# mapleSDuino-V0_1_013-eagle7.net
KiCad netlist of a schematic drawn in EAGLE
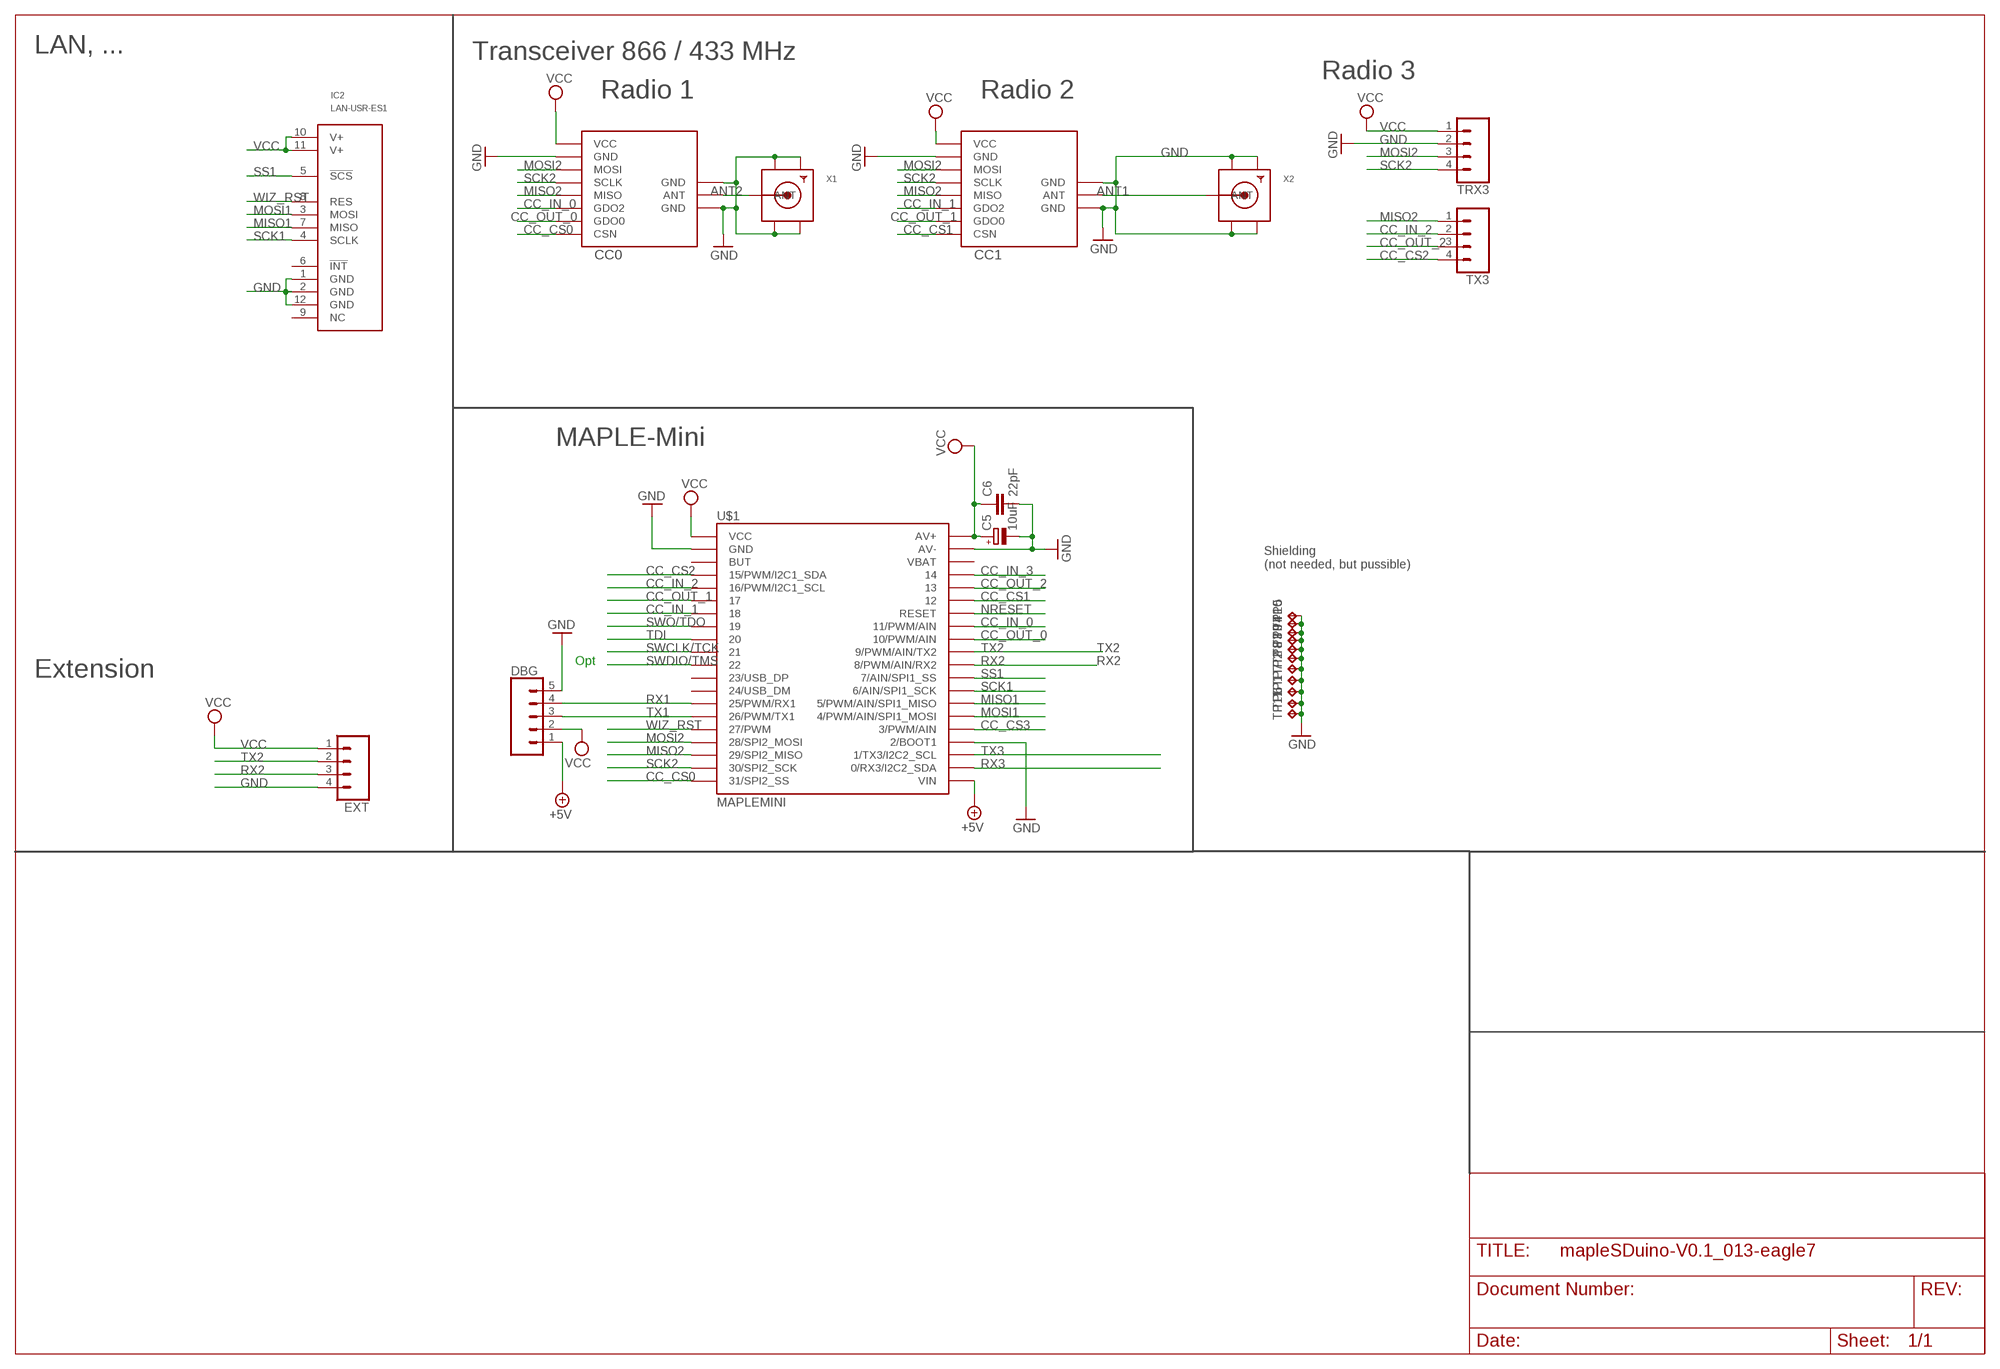
[diagram p0: schematic, sheet 1]

(export (version "E")
  (design (tool "Eeschema 10.0.6"))
  (components
    (comp (ref "C5")
      (value "10uF")
      (footprint "eagle-import:R_2012-12W")
      (libsource (lib "eagle-import") (part "CPOL-EUR/2012-12W"))
    )
    (comp (ref "C6")
      (value "22pF")
      (footprint "eagle-import:C0805")
      (libsource (lib "eagle-import") (part "C-EUC0805"))
    )
    (comp (ref "CC0")
      (value "CC1101")
      (footprint "eagle-import:CC1101_MODULE1_SMD")
      (libsource (lib "eagle-import") (part "CC1101_MODULE1SMD"))
    )
    (comp (ref "CC1")
      (value "CC1101_MODULE1SMD")
      (footprint "eagle-import:CC1101_MODULE1_SMD")
      (libsource (lib "eagle-import") (part "CC1101_MODULE1SMD"))
    )
    (comp (ref "DBG")
      (value "CONN_05LOCK")
      (footprint "eagle-import:1X05_LOCK")
      (libsource (lib "eagle-import") (part "CONN_05LOCK"))
    )
    (comp (ref "EXT")
      (value "CONN_04PTH")
      (footprint "eagle-import:1X04")
      (libsource (lib "eagle-import") (part "CONN_04PTH"))
    )
    (comp (ref "IC2")
      (value "LAN-USR-ES1")
      (footprint "eagle-import:USR-ES1")
      (libsource (lib "eagle-import") (part "LAN-USR-ES1"))
    )
    (comp (ref "TP1")
      (value "TPTP06SQ")
      (footprint "eagle-import:TP06SQ")
      (libsource (lib "eagle-import") (part "TPTP06SQ"))
    )
    (comp (ref "TP2")
      (value "TPTP06SQ")
      (footprint "eagle-import:TP06SQ")
      (libsource (lib "eagle-import") (part "TPTP06SQ"))
    )
    (comp (ref "TP3")
      (value "TPTP06SQ")
      (footprint "eagle-import:TP06SQ")
      (libsource (lib "eagle-import") (part "TPTP06SQ"))
    )
    (comp (ref "TP4")
      (value "TPTP06SQ")
      (footprint "eagle-import:TP06SQ")
      (libsource (lib "eagle-import") (part "TPTP06SQ"))
    )
    (comp (ref "TP5")
      (value "TPTP06SQ")
      (footprint "eagle-import:TP06SQ")
      (libsource (lib "eagle-import") (part "TPTP06SQ"))
    )
    (comp (ref "TP6")
      (value "TPTP06SQ")
      (footprint "eagle-import:TP06SQ")
      (libsource (lib "eagle-import") (part "TPTP06SQ"))
    )
    (comp (ref "TP7")
      (value "TPTP06SQ")
      (footprint "eagle-import:TP06SQ")
      (libsource (lib "eagle-import") (part "TPTP06SQ"))
    )
    (comp (ref "TP8")
      (value "TPTP06SQ")
      (footprint "eagle-import:TP06SQ")
      (libsource (lib "eagle-import") (part "TPTP06SQ"))
    )
    (comp (ref "TP9")
      (value "TPTP06SQ")
      (footprint "eagle-import:TP06SQ")
      (libsource (lib "eagle-import") (part "TPTP06SQ"))
    )
    (comp (ref "TP10")
      (value "TPTP06SQ")
      (footprint "eagle-import:TP06SQ")
      (libsource (lib "eagle-import") (part "TPTP06SQ"))
    )
    (comp (ref "TP11")
      (value "TPTP06SQ")
      (footprint "eagle-import:TP06SQ")
      (libsource (lib "eagle-import") (part "TPTP06SQ"))
    )
    (comp (ref "TRX3")
      (value "CONN_04PTH")
      (footprint "eagle-import:1X04")
      (libsource (lib "eagle-import") (part "CONN_04PTH"))
    )
    (comp (ref "TX3")
      (value "CONN_04PTH")
      (footprint "eagle-import:1X04")
      (libsource (lib "eagle-import") (part "CONN_04PTH"))
    )
    (comp (ref "U$1")
      (value "MAPLEMINI")
      (footprint "eagle-import:20-DIP")
      (libsource (lib "eagle-import") (part "MAPLEMINI"))
    )
    (comp (ref "X1")
      (value "SMACONNECTOR_EDGE")
      (footprint "eagle-import:SMA_EDGELAUNCH")
      (libsource (lib "eagle-import") (part "SMACONNECTOR_EDGE"))
    )
    (comp (ref "X2")
      (value "SMACONNECTOR_EDGE")
      (footprint "eagle-import:SMA_EDGELAUNCH")
      (libsource (lib "eagle-import") (part "SMACONNECTOR_EDGE"))
    )
  )
  (nets
    (net (code "1") (name "+5V") (class "Default")
      (node (ref "DBG") (pin "1") (pinfunction "1_1") (pintype "passive"))
      (node (ref "U$1") (pin "21") (pinfunction "VIN_21") (pintype "bidirectional"))
    )
    (net (code "2") (name "/ANT1") (class "Default")
      (node (ref "CC1") (pin "ANT") (pinfunction "ANT_ANT") (pintype "output"))
      (node (ref "X2") (pin "P") (pinfunction "ANT_P") (pintype "bidirectional"))
    )
    (net (code "3") (name "/ANT2") (class "Default")
      (node (ref "CC0") (pin "ANT") (pinfunction "ANT_ANT") (pintype "output"))
      (node (ref "X1") (pin "P") (pinfunction "ANT_P") (pintype "bidirectional"))
    )
    (net (code "4") (name "/CC_CS0") (class "Default")
      (node (ref "CC0") (pin "CSN") (pinfunction "CSN_CSN") (pintype "bidirectional"))
      (node (ref "U$1") (pin "20") (pinfunction "31/SPI2_SS_20") (pintype "bidirectional"))
    )
    (net (code "5") (name "/CC_CS1") (class "Default")
      (node (ref "CC1") (pin "CSN") (pinfunction "CSN_CSN") (pintype "bidirectional"))
      (node (ref "U$1") (pin "35") (pinfunction "12_35") (pintype "bidirectional"))
    )
    (net (code "6") (name "/CC_CS2") (class "Default")
      (node (ref "TX3") (pin "4") (pinfunction "4_4") (pintype "passive"))
      (node (ref "U$1") (pin "4") (pinfunction "15/PWM/I2C1_SDA_4") (pintype "bidirectional"))
    )
    (net (code "7") (name "/CC_CS3") (class "Default")
      (node (ref "U$1") (pin "25") (pinfunction "3/PWM/AIN_25") (pintype "bidirectional"))
    )
    (net (code "8") (name "/CC_IN_0") (class "Default")
      (node (ref "CC0") (pin "GDO2") (pinfunction "GDO2_GDO2") (pintype "bidirectional"))
      (node (ref "U$1") (pin "33") (pinfunction "11/PWM/AIN_33") (pintype "bidirectional"))
    )
    (net (code "9") (name "/CC_IN_1") (class "Default")
      (node (ref "CC1") (pin "GDO2") (pinfunction "GDO2_GDO2") (pintype "bidirectional"))
      (node (ref "U$1") (pin "7") (pinfunction "18_7") (pintype "bidirectional"))
    )
    (net (code "10") (name "/CC_IN_2") (class "Default")
      (node (ref "TX3") (pin "2") (pinfunction "2_2") (pintype "passive"))
      (node (ref "U$1") (pin "5") (pinfunction "16/PWM/I2C1_SCL_5") (pintype "bidirectional"))
    )
    (net (code "11") (name "/CC_IN_3") (class "Default")
      (node (ref "U$1") (pin "37") (pinfunction "14_37") (pintype "bidirectional"))
    )
    (net (code "12") (name "/CC_OUT_0") (class "Default")
      (node (ref "CC0") (pin "GDO0") (pinfunction "GDO0_GDO0") (pintype "bidirectional"))
      (node (ref "U$1") (pin "32") (pinfunction "10/PWM/AIN_32") (pintype "bidirectional"))
    )
    (net (code "13") (name "/CC_OUT_1") (class "Default")
      (node (ref "CC1") (pin "GDO0") (pinfunction "GDO0_GDO0") (pintype "bidirectional"))
      (node (ref "U$1") (pin "6") (pinfunction "17_6") (pintype "bidirectional"))
    )
    (net (code "14") (name "/CC_OUT_2") (class "Default")
      (node (ref "TX3") (pin "3") (pinfunction "3_3") (pintype "passive"))
      (node (ref "U$1") (pin "36") (pinfunction "13_36") (pintype "bidirectional"))
    )
    (net (code "15") (name "/MISO1") (class "Default")
      (node (ref "IC2") (pin "7") (pinfunction "MISO_7") (pintype "bidirectional"))
      (node (ref "U$1") (pin "27") (pinfunction "5/PWM/AIN/SPI1_MISO_27") (pintype "bidirectional"))
    )
    (net (code "16") (name "/MISO2") (class "Default")
      (node (ref "CC0") (pin "MISO") (pinfunction "MISO_MISO") (pintype "bidirectional"))
      (node (ref "CC1") (pin "MISO") (pinfunction "MISO_MISO") (pintype "bidirectional"))
      (node (ref "TX3") (pin "1") (pinfunction "1_1") (pintype "passive"))
      (node (ref "U$1") (pin "18") (pinfunction "29/SPI2_MISO_18") (pintype "bidirectional"))
    )
    (net (code "17") (name "/MOSI1") (class "Default")
      (node (ref "IC2") (pin "3") (pinfunction "MOSI_3") (pintype "bidirectional"))
      (node (ref "U$1") (pin "26") (pinfunction "4/PWM/AIN/SPI1_MOSI_26") (pintype "bidirectional"))
    )
    (net (code "18") (name "/MOSI2") (class "Default")
      (node (ref "CC0") (pin "MOSI") (pinfunction "MOSI_MOSI") (pintype "bidirectional"))
      (node (ref "CC1") (pin "MOSI") (pinfunction "MOSI_MOSI") (pintype "bidirectional"))
      (node (ref "TRX3") (pin "3") (pinfunction "3_3") (pintype "passive"))
      (node (ref "U$1") (pin "17") (pinfunction "28/SPI2_MOSI_17") (pintype "bidirectional"))
    )
    (net (code "19") (name "/NRESET") (class "Default")
      (node (ref "U$1") (pin "34") (pinfunction "RESET_34") (pintype "bidirectional"))
    )
    (net (code "20") (name "/RX1") (class "Default")
      (node (ref "DBG") (pin "4") (pinfunction "4_4") (pintype "passive"))
      (node (ref "U$1") (pin "14") (pinfunction "25/PWM/RX1_14") (pintype "bidirectional"))
    )
    (net (code "21") (name "/RX2") (class "Default")
      (node (ref "EXT") (pin "3") (pinfunction "3_3") (pintype "passive"))
      (node (ref "U$1") (pin "30") (pinfunction "8/PWM/AIN/RX2_30") (pintype "bidirectional"))
    )
    (net (code "22") (name "/RX3") (class "Default")
      (node (ref "U$1") (pin "22") (pinfunction "0/RX3/I2C2_SDA_22") (pintype "bidirectional"))
    )
    (net (code "23") (name "/SCK1") (class "Default")
      (node (ref "IC2") (pin "4") (pinfunction "SCLK_4") (pintype "input"))
      (node (ref "U$1") (pin "28") (pinfunction "6/AIN/SPI1_SCK_28") (pintype "bidirectional"))
    )
    (net (code "24") (name "/SCK2") (class "Default")
      (node (ref "CC0") (pin "SCLK") (pinfunction "SCLK_SCLK") (pintype "bidirectional"))
      (node (ref "CC1") (pin "SCLK") (pinfunction "SCLK_SCLK") (pintype "bidirectional"))
      (node (ref "TRX3") (pin "4") (pinfunction "4_4") (pintype "passive"))
      (node (ref "U$1") (pin "19") (pinfunction "30/SPI2_SCK_19") (pintype "bidirectional"))
    )
    (net (code "25") (name "/SS1") (class "Default")
      (node (ref "IC2") (pin "5") (pinfunction "~{SCS}_5") (pintype "input"))
      (node (ref "U$1") (pin "29") (pinfunction "7/AIN/SPI1_SS_29") (pintype "bidirectional"))
    )
    (net (code "26") (name "/SWCLK{slash}TCK") (class "Default")
      (node (ref "U$1") (pin "10") (pinfunction "21_10") (pintype "bidirectional"))
    )
    (net (code "27") (name "/SWDIO{slash}TMS") (class "Default")
      (node (ref "U$1") (pin "11") (pinfunction "22_11") (pintype "bidirectional"))
    )
    (net (code "28") (name "/SWO{slash}TDO") (class "Default")
      (node (ref "U$1") (pin "8") (pinfunction "19_8") (pintype "bidirectional"))
    )
    (net (code "29") (name "/TDI") (class "Default")
      (node (ref "U$1") (pin "9") (pinfunction "20_9") (pintype "bidirectional"))
    )
    (net (code "30") (name "/TX1") (class "Default")
      (node (ref "DBG") (pin "3") (pinfunction "3_3") (pintype "passive"))
      (node (ref "U$1") (pin "15") (pinfunction "26/PWM/TX1_15") (pintype "bidirectional"))
    )
    (net (code "31") (name "/TX2") (class "Default")
      (node (ref "EXT") (pin "2") (pinfunction "2_2") (pintype "passive"))
      (node (ref "U$1") (pin "31") (pinfunction "9/PWM/AIN/TX2_31") (pintype "bidirectional"))
    )
    (net (code "32") (name "/TX3") (class "Default")
      (node (ref "U$1") (pin "23") (pinfunction "1/TX3/I2C2_SCL_23") (pintype "bidirectional"))
    )
    (net (code "33") (name "/WIZ_RST") (class "Default")
      (node (ref "IC2") (pin "8") (pinfunction "RES_8") (pintype "input"))
      (node (ref "U$1") (pin "16") (pinfunction "27/PWM_16") (pintype "bidirectional"))
    )
    (net (code "34") (name "GND") (class "Default")
      (node (ref "C5") (pin "-") (pinfunction "-_-") (pintype "passive"))
      (node (ref "C6") (pin "2") (pinfunction "2_2") (pintype "passive"))
      (node (ref "CC0") (pin "GND@0") (pinfunction "GND_GND@0") (pintype "power_in"))
      (node (ref "CC0") (pin "GND@1") (pinfunction "GND_GND@1") (pintype "power_in"))
      (node (ref "CC0") (pin "GND@2") (pinfunction "GND_GND@2") (pintype "power_in"))
      (node (ref "CC1") (pin "GND@0") (pinfunction "GND_GND@0") (pintype "power_in"))
      (node (ref "CC1") (pin "GND@1") (pinfunction "GND_GND@1") (pintype "power_in"))
      (node (ref "CC1") (pin "GND@2") (pinfunction "GND_GND@2") (pintype "power_in"))
      (node (ref "DBG") (pin "5") (pinfunction "5_5") (pintype "passive"))
      (node (ref "EXT") (pin "4") (pinfunction "4_4") (pintype "passive"))
      (node (ref "IC2") (pin "1") (pinfunction "GND_1") (pintype "power_in"))
      (node (ref "IC2") (pin "12") (pinfunction "GND_12") (pintype "power_in"))
      (node (ref "IC2") (pin "2") (pinfunction "GND_2") (pintype "power_in"))
      (node (ref "TP1") (pin "TP") (pinfunction "TP_TP") (pintype "input"))
      (node (ref "TP10") (pin "TP") (pinfunction "TP_TP") (pintype "input"))
      (node (ref "TP11") (pin "TP") (pinfunction "TP_TP") (pintype "input"))
      (node (ref "TP2") (pin "TP") (pinfunction "TP_TP") (pintype "input"))
      (node (ref "TP3") (pin "TP") (pinfunction "TP_TP") (pintype "input"))
      (node (ref "TP4") (pin "TP") (pinfunction "TP_TP") (pintype "input"))
      (node (ref "TP5") (pin "TP") (pinfunction "TP_TP") (pintype "input"))
      (node (ref "TP6") (pin "TP") (pinfunction "TP_TP") (pintype "input"))
      (node (ref "TP7") (pin "TP") (pinfunction "TP_TP") (pintype "input"))
      (node (ref "TP8") (pin "TP") (pinfunction "TP_TP") (pintype "input"))
      (node (ref "TP9") (pin "TP") (pinfunction "TP_TP") (pintype "input"))
      (node (ref "TRX3") (pin "2") (pinfunction "2_2") (pintype "passive"))
      (node (ref "U$1") (pin "2") (pinfunction "GND_2") (pintype "bidirectional"))
      (node (ref "U$1") (pin "24") (pinfunction "2/BOOT1_24") (pintype "bidirectional"))
      (node (ref "U$1") (pin "39") (pinfunction "AV-_39") (pintype "bidirectional"))
      (node (ref "X1") (pin "GND@1") (pinfunction "GND4_GND@1") (pintype "power_in"))
      (node (ref "X1") (pin "GND@2") (pinfunction "GND3_GND@2") (pintype "power_in"))
      (node (ref "X1") (pin "GND@3") (pinfunction "GND2_GND@3") (pintype "power_in"))
      (node (ref "X1") (pin "GND@4") (pinfunction "GND1_GND@4") (pintype "power_in"))
      (node (ref "X2") (pin "GND@1") (pinfunction "GND4_GND@1") (pintype "power_in"))
      (node (ref "X2") (pin "GND@2") (pinfunction "GND3_GND@2") (pintype "power_in"))
      (node (ref "X2") (pin "GND@3") (pinfunction "GND2_GND@3") (pintype "power_in"))
      (node (ref "X2") (pin "GND@4") (pinfunction "GND1_GND@4") (pintype "power_in"))
    )
    (net (code "35") (name "VCC") (class "Default")
      (node (ref "C5") (pin "+") (pinfunction "+_+") (pintype "passive"))
      (node (ref "C6") (pin "1") (pinfunction "1_1") (pintype "passive"))
      (node (ref "CC0") (pin "VCC") (pinfunction "VCC_VCC") (pintype "power_in"))
      (node (ref "CC1") (pin "VCC") (pinfunction "VCC_VCC") (pintype "power_in"))
      (node (ref "DBG") (pin "2") (pinfunction "2_2") (pintype "passive"))
      (node (ref "EXT") (pin "1") (pinfunction "1_1") (pintype "passive"))
      (node (ref "IC2") (pin "10") (pinfunction "V+_10") (pintype "power_in"))
      (node (ref "IC2") (pin "11") (pinfunction "V+_11") (pintype "power_in"))
      (node (ref "TRX3") (pin "1") (pinfunction "1_1") (pintype "passive"))
      (node (ref "U$1") (pin "1") (pinfunction "VCC_1") (pintype "bidirectional"))
      (node (ref "U$1") (pin "40") (pinfunction "AV+_40") (pintype "bidirectional"))
    )
    (net (code "36") (name "unconnected-(IC2-NC-Pad9)") (class "Default")
      (node (ref "IC2") (pin "9") (pinfunction "NC_9") (pintype "no_connect"))
    )
    (net (code "37") (name "unconnected-(IC2-~{INT}-Pad6)") (class "Default")
      (node (ref "IC2") (pin "6") (pinfunction "~{INT}_6") (pintype "output"))
    )
    (net (code "38") (name "unconnected-(U$1-23{slash}USB_DP-Pad12)") (class "Default")
      (node (ref "U$1") (pin "12") (pinfunction "23/USB_DP_12") (pintype "bidirectional"))
    )
    (net (code "39") (name "unconnected-(U$1-24{slash}USB_DM-Pad13)") (class "Default")
      (node (ref "U$1") (pin "13") (pinfunction "24/USB_DM_13") (pintype "bidirectional"))
    )
    (net (code "40") (name "unconnected-(U$1-BUT-Pad3)") (class "Default")
      (node (ref "U$1") (pin "3") (pinfunction "BUT_3") (pintype "bidirectional"))
    )
    (net (code "41") (name "unconnected-(U$1-VBAT-Pad38)") (class "Default")
      (node (ref "U$1") (pin "38") (pinfunction "VBAT_38") (pintype "bidirectional"))
    )
  )
)
